# R409H.net
KiCad netlist of a schematic drawn in EAGLE
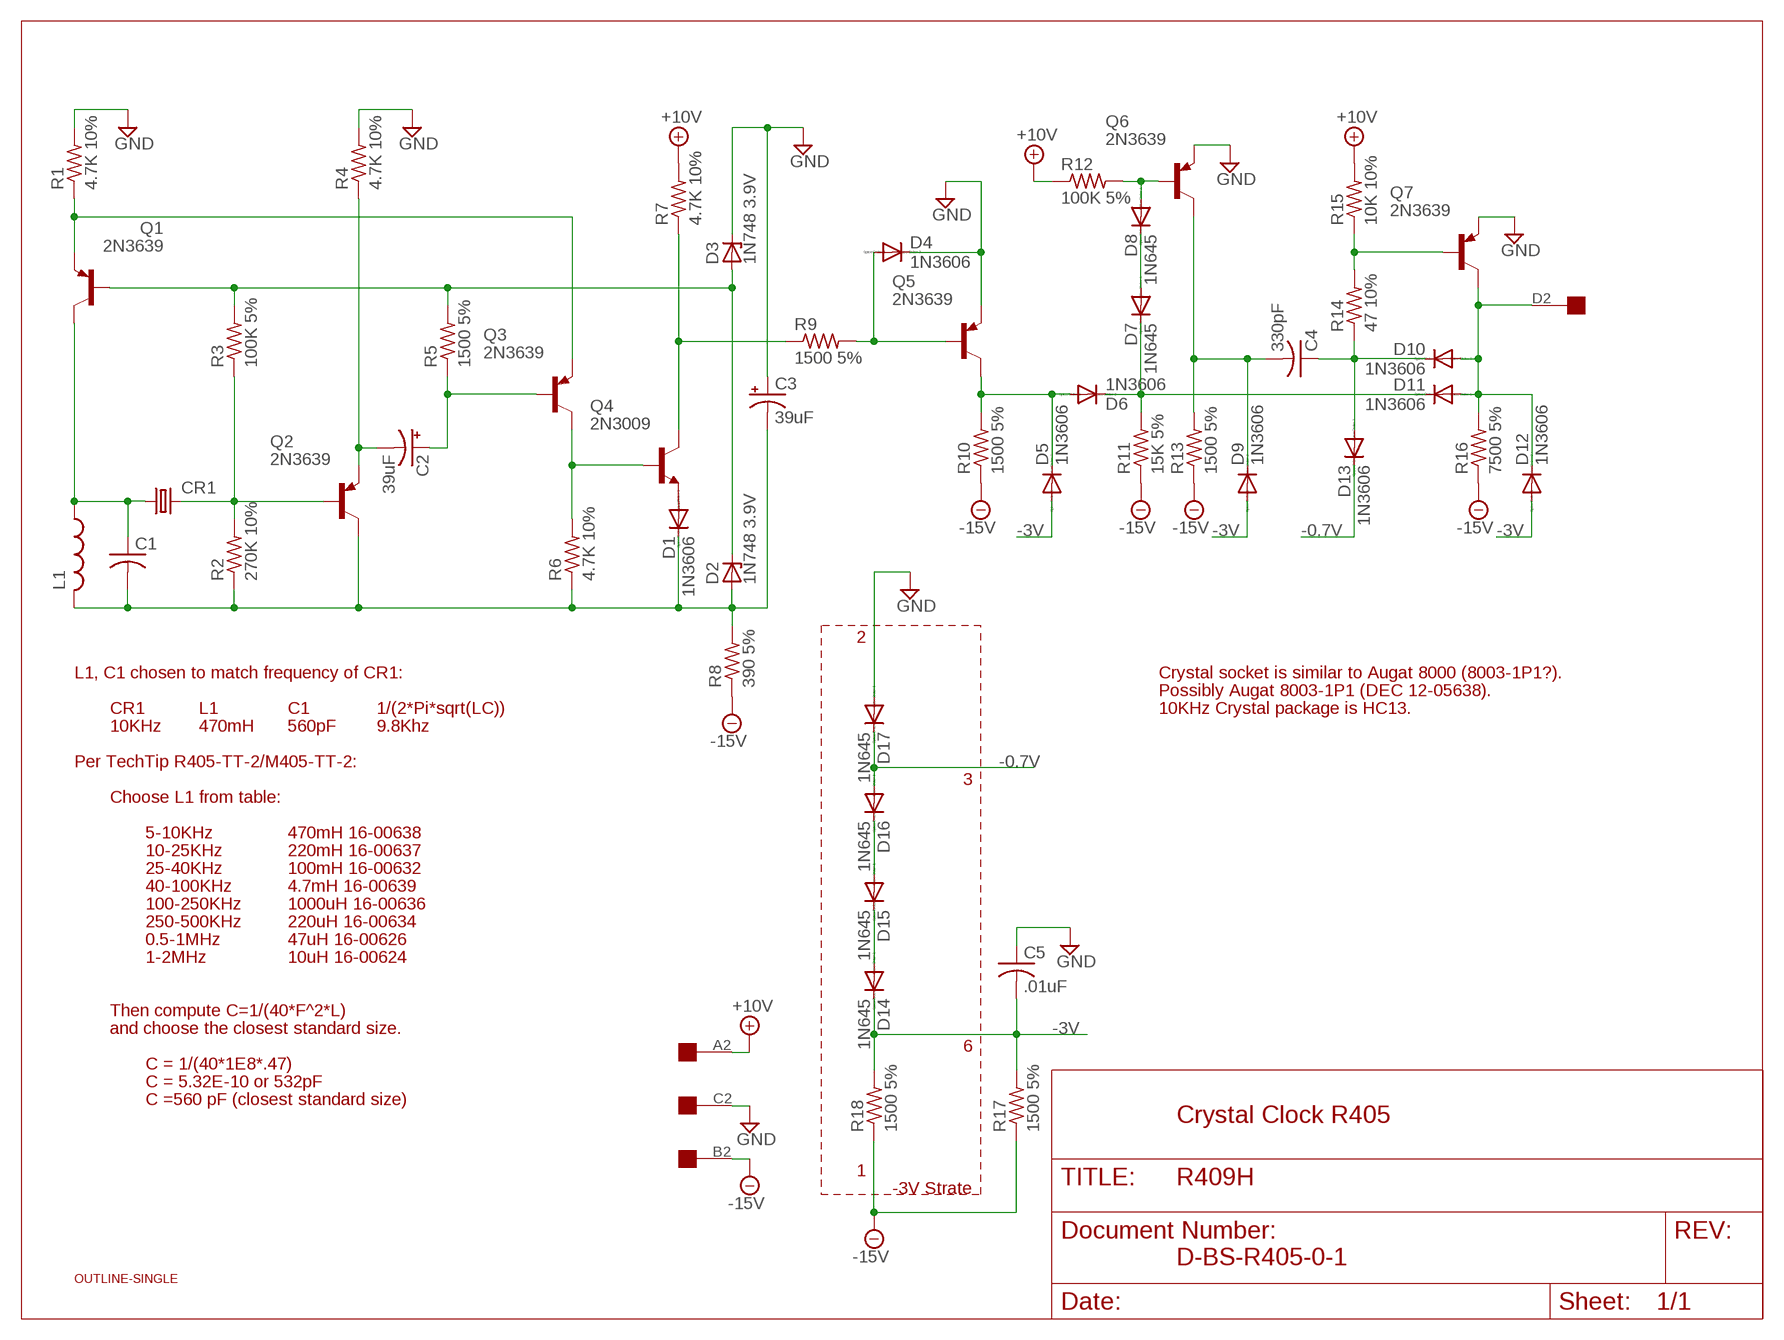
[diagram p0: schematic, sheet 1]

(export (version "E")
  (design (tool "Eeschema 10.0.6"))
  (components
    (comp (ref "C1")
      (value "C-US150-054X183")
      (footprint "eagle-import:C150-054X183")
      (libsource (lib "eagle-import") (part "C-US150-054X183"))
    )
    (comp (ref "C2")
      (value "39uF")
      (footprint "eagle-import:E15-5")
      (libsource (lib "eagle-import") (part "CPOL-USE15-5AXIAL"))
    )
    (comp (ref "C3")
      (value "39uF")
      (footprint "eagle-import:E15-5")
      (libsource (lib "eagle-import") (part "CPOL-USE15-5AXIAL"))
    )
    (comp (ref "C4")
      (value "330pF")
      (footprint "eagle-import:C150-054X183")
      (libsource (lib "eagle-import") (part "C-US150-054X183"))
    )
    (comp (ref "C5")
      (value ".01uF")
      (footprint "eagle-import:C150-054X183")
      (libsource (lib "eagle-import") (part "C-US150-054X183"))
    )
    (comp (ref "CR1")
      (value "CRYTALHC13U-H")
      (footprint "eagle-import:HC13U-H")
      (libsource (lib "eagle-import") (part "CRYTALHC13U-H"))
    )
    (comp (ref "D1")
      (value "1N3606")
      (footprint "eagle-import:DO35-10")
      (libsource (lib "eagle-import") (part "1N4148DO35-10"))
    )
    (comp (ref "D2")
      (value "1N748 3.9V")
      (footprint "eagle-import:DO35Z10")
      (libsource (lib "eagle-import") (part "ZENER-DIODEDO35Z10"))
    )
    (comp (ref "D3")
      (value "1N748 3.9V")
      (footprint "eagle-import:DO35Z10")
      (libsource (lib "eagle-import") (part "ZENER-DIODEDO35Z10"))
    )
    (comp (ref "D4")
      (value "1N3606")
      (footprint "eagle-import:DO35-10")
      (libsource (lib "eagle-import") (part "1N4148DO35-10"))
    )
    (comp (ref "D5")
      (value "1N3606")
      (footprint "eagle-import:DO35-10")
      (libsource (lib "eagle-import") (part "1N4148DO35-10"))
    )
    (comp (ref "D6")
      (value "1N3606")
      (footprint "eagle-import:DO35-10")
      (libsource (lib "eagle-import") (part "1N4148DO35-10"))
    )
    (comp (ref "D7")
      (value "1N645")
      (footprint "eagle-import:DO35-10")
      (libsource (lib "eagle-import") (part "1N4148DO35-10"))
    )
    (comp (ref "D8")
      (value "1N645")
      (footprint "eagle-import:DO35-10")
      (libsource (lib "eagle-import") (part "1N4148DO35-10"))
    )
    (comp (ref "D9")
      (value "1N3606")
      (footprint "eagle-import:DO35-10")
      (libsource (lib "eagle-import") (part "1N4148DO35-10"))
    )
    (comp (ref "D10")
      (value "1N3606")
      (footprint "eagle-import:DO35-10")
      (libsource (lib "eagle-import") (part "1N4148DO35-10"))
    )
    (comp (ref "D11")
      (value "1N3606")
      (footprint "eagle-import:DO35-10")
      (libsource (lib "eagle-import") (part "1N4148DO35-10"))
    )
    (comp (ref "D12")
      (value "1N3606")
      (footprint "eagle-import:DO35-10")
      (libsource (lib "eagle-import") (part "1N4148DO35-10"))
    )
    (comp (ref "D13")
      (value "1N3606")
      (footprint "eagle-import:DO35-10")
      (libsource (lib "eagle-import") (part "1N4148DO35-10"))
    )
    (comp (ref "D14")
      (value "1N645")
      (footprint "eagle-import:DO35-10")
      (libsource (lib "eagle-import") (part "1N4148DO35-10"))
    )
    (comp (ref "D15")
      (value "1N645")
      (footprint "eagle-import:DO35-10")
      (libsource (lib "eagle-import") (part "1N4148DO35-10"))
    )
    (comp (ref "D16")
      (value "1N645")
      (footprint "eagle-import:DO35-10")
      (libsource (lib "eagle-import") (part "1N4148DO35-10"))
    )
    (comp (ref "D17")
      (value "1N645")
      (footprint "eagle-import:DO35-10")
      (libsource (lib "eagle-import") (part "1N4148DO35-10"))
    )
    (comp (ref "L1")
      (value "L-US0207/7")
      (footprint "eagle-import:0207_7")
      (libsource (lib "eagle-import") (part "L-US0207/7"))
    )
    (comp (ref "Q1")
      (value "2N3639")
      (footprint "eagle-import:TO39")
      (libsource (lib "eagle-import") (part "2N2904"))
    )
    (comp (ref "Q2")
      (value "2N3639")
      (footprint "eagle-import:TO39")
      (libsource (lib "eagle-import") (part "2N2904"))
    )
    (comp (ref "Q3")
      (value "2N3639")
      (footprint "eagle-import:TO39")
      (libsource (lib "eagle-import") (part "2N2904"))
    )
    (comp (ref "Q4")
      (value "2N3009")
      (footprint "eagle-import:TO5")
      (libsource (lib "eagle-import") (part "2N2102"))
    )
    (comp (ref "Q5")
      (value "2N3639")
      (footprint "eagle-import:TO39")
      (libsource (lib "eagle-import") (part "2N2904"))
    )
    (comp (ref "Q6")
      (value "2N3639")
      (footprint "eagle-import:TO39")
      (libsource (lib "eagle-import") (part "2N2904"))
    )
    (comp (ref "Q7")
      (value "2N3639")
      (footprint "eagle-import:TO39")
      (libsource (lib "eagle-import") (part "2N2904"))
    )
    (comp (ref "R1")
      (value "4.7K 10%")
      (footprint "eagle-import:0207_10")
      (libsource (lib "eagle-import") (part "R-US_0207/10"))
    )
    (comp (ref "R2")
      (value "270K 10%")
      (footprint "eagle-import:0207_10")
      (libsource (lib "eagle-import") (part "R-US_0207/10"))
    )
    (comp (ref "R3")
      (value "100K 5%")
      (footprint "eagle-import:0207_10")
      (libsource (lib "eagle-import") (part "R-US_0207/10"))
    )
    (comp (ref "R4")
      (value "4.7K 10%")
      (footprint "eagle-import:0207_10")
      (libsource (lib "eagle-import") (part "R-US_0207/10"))
    )
    (comp (ref "R5")
      (value "1500 5%")
      (footprint "eagle-import:0207_10")
      (libsource (lib "eagle-import") (part "R-US_0207/10"))
    )
    (comp (ref "R6")
      (value "4.7K 10%")
      (footprint "eagle-import:0207_10")
      (libsource (lib "eagle-import") (part "R-US_0207/10"))
    )
    (comp (ref "R7")
      (value "4.7K 10%")
      (footprint "eagle-import:0207_10")
      (libsource (lib "eagle-import") (part "R-US_0207/10"))
    )
    (comp (ref "R8")
      (value "390 5%")
      (footprint "eagle-import:0207_10")
      (libsource (lib "eagle-import") (part "R-US_0207/10"))
    )
    (comp (ref "R9")
      (value "1500 5%")
      (footprint "eagle-import:0207_10")
      (libsource (lib "eagle-import") (part "R-US_0207/10"))
    )
    (comp (ref "R10")
      (value "1500 5%")
      (footprint "eagle-import:0207_10")
      (libsource (lib "eagle-import") (part "R-US_0207/10"))
    )
    (comp (ref "R11")
      (value "15K 5%")
      (footprint "eagle-import:0207_10")
      (libsource (lib "eagle-import") (part "R-US_0207/10"))
    )
    (comp (ref "R12")
      (value "100K 5%")
      (footprint "eagle-import:0207_10")
      (libsource (lib "eagle-import") (part "R-US_0207/10"))
    )
    (comp (ref "R13")
      (value "1500 5%")
      (footprint "eagle-import:0207_10")
      (libsource (lib "eagle-import") (part "R-US_0207/10"))
    )
    (comp (ref "R14")
      (value "47 10%")
      (footprint "eagle-import:0207_10")
      (libsource (lib "eagle-import") (part "R-US_0207/10"))
    )
    (comp (ref "R15")
      (value "10K 10%")
      (footprint "eagle-import:0207_10")
      (libsource (lib "eagle-import") (part "R-US_0207/10"))
    )
    (comp (ref "R16")
      (value "7500 5%")
      (footprint "eagle-import:0207_10")
      (libsource (lib "eagle-import") (part "R-US_0207/10"))
    )
    (comp (ref "R17")
      (value "1500 5%")
      (footprint "eagle-import:0207_10")
      (libsource (lib "eagle-import") (part "R-US_0207/10"))
    )
    (comp (ref "R18")
      (value "1500 5%")
      (footprint "eagle-import:0207_10")
      (libsource (lib "eagle-import") (part "R-US_0207/10"))
    )
    (comp (ref "U$1")
      (value "OUTLINE-SINGLE")
      (footprint "eagle-import:SINGLE")
      (libsource (lib "eagle-import") (part "OUTLINE-SINGLE"))
    )
    (comp (ref "U$2")
      (value "EDGE-1")
      (footprint "eagle-import:EDGE-CON1")
      (libsource (lib "eagle-import") (part "EDGE-1"))
    )
  )
  (nets
    (net (code "1") (name "+10V") (class "Default")
      (node (ref "R12") (pin "1") (pinfunction "1_1") (pintype "passive"))
      (node (ref "R15") (pin "2") (pinfunction "2_2") (pintype "passive"))
      (node (ref "R7") (pin "2") (pinfunction "2_2") (pintype "passive"))
      (node (ref "U$2") (pin "A2") (pinfunction "1_A2") (pintype "bidirectional"))
    )
    (net (code "2") (name "-15V") (class "Default")
      (node (ref "R10") (pin "1") (pinfunction "1_1") (pintype "passive"))
      (node (ref "R11") (pin "1") (pinfunction "1_1") (pintype "passive"))
      (node (ref "R13") (pin "1") (pinfunction "1_1") (pintype "passive"))
      (node (ref "R16") (pin "1") (pinfunction "1_1") (pintype "passive"))
      (node (ref "R17") (pin "1") (pinfunction "1_1") (pintype "passive"))
      (node (ref "R18") (pin "1") (pinfunction "1_1") (pintype "passive"))
      (node (ref "R8") (pin "1") (pinfunction "1_1") (pintype "passive"))
      (node (ref "U$2") (pin "B2") (pinfunction "1_B2") (pintype "bidirectional"))
    )
    (net (code "3") (name "/-0.7V") (class "Default")
      (node (ref "D13") (pin "C") (pinfunction "C_C") (pintype "passive"))
      (node (ref "D16") (pin "A") (pinfunction "A_A") (pintype "passive"))
      (node (ref "D17") (pin "C") (pinfunction "C_C") (pintype "passive"))
    )
    (net (code "4") (name "/-3V") (class "Default")
      (node (ref "C5") (pin "2") (pinfunction "2_2") (pintype "passive"))
      (node (ref "D12") (pin "A") (pinfunction "A_A") (pintype "passive"))
      (node (ref "D14") (pin "C") (pinfunction "C_C") (pintype "passive"))
      (node (ref "D5") (pin "A") (pinfunction "A_A") (pintype "passive"))
      (node (ref "D9") (pin "A") (pinfunction "A_A") (pintype "passive"))
      (node (ref "R17") (pin "2") (pinfunction "2_2") (pintype "passive"))
      (node (ref "R18") (pin "2") (pinfunction "2_2") (pintype "passive"))
    )
    (net (code "5") (name "GND") (class "Default")
      (node (ref "C3") (pin "+") (pinfunction "+_+") (pintype "passive"))
      (node (ref "C5") (pin "1") (pinfunction "1_1") (pintype "passive"))
      (node (ref "D17") (pin "A") (pinfunction "A_A") (pintype "passive"))
      (node (ref "D3") (pin "C") (pinfunction "C_C") (pintype "passive"))
      (node (ref "D4") (pin "C") (pinfunction "C_C") (pintype "passive"))
      (node (ref "Q5") (pin "1") (pinfunction "E_1") (pintype "passive"))
      (node (ref "Q6") (pin "1") (pinfunction "E_1") (pintype "passive"))
      (node (ref "Q7") (pin "1") (pinfunction "E_1") (pintype "passive"))
      (node (ref "R1") (pin "2") (pinfunction "2_2") (pintype "passive"))
      (node (ref "R4") (pin "2") (pinfunction "2_2") (pintype "passive"))
      (node (ref "U$2") (pin "C2") (pinfunction "1_C2") (pintype "bidirectional"))
    )
    (net (code "6") (name "Net-(C4-Pad1)") (class "Default")
      (node (ref "C4") (pin "1") (pinfunction "1_1") (pintype "passive"))
      (node (ref "D10") (pin "C") (pinfunction "C_C") (pintype "passive"))
      (node (ref "D13") (pin "A") (pinfunction "A_A") (pintype "passive"))
      (node (ref "R14") (pin "1") (pinfunction "1_1") (pintype "passive"))
    )
    (net (code "7") (name "Net-(D7-PadA)") (class "Default")
      (node (ref "D7") (pin "A") (pinfunction "A_A") (pintype "passive"))
      (node (ref "D8") (pin "C") (pinfunction "C_C") (pintype "passive"))
    )
    (net (code "8") (name "Net-(D11-PadC)") (class "Default")
      (node (ref "D11") (pin "C") (pinfunction "C_C") (pintype "passive"))
      (node (ref "D6") (pin "C") (pinfunction "C_C") (pintype "passive"))
      (node (ref "D7") (pin "C") (pinfunction "C_C") (pintype "passive"))
      (node (ref "R11") (pin "2") (pinfunction "2_2") (pintype "passive"))
    )
    (net (code "9") (name "Net-(D14-PadA)") (class "Default")
      (node (ref "D14") (pin "A") (pinfunction "A_A") (pintype "passive"))
      (node (ref "D15") (pin "C") (pinfunction "C_C") (pintype "passive"))
    )
    (net (code "10") (name "Net-(D15-PadA)") (class "Default")
      (node (ref "D15") (pin "A") (pinfunction "A_A") (pintype "passive"))
      (node (ref "D16") (pin "C") (pinfunction "C_C") (pintype "passive"))
    )
    (net (code "11") (name "Net-(Q1-B)") (class "Default")
      (node (ref "D2") (pin "C") (pinfunction "C_C") (pintype "passive"))
      (node (ref "D3") (pin "A") (pinfunction "A_A") (pintype "passive"))
      (node (ref "Q1") (pin "2") (pinfunction "B_2") (pintype "passive"))
      (node (ref "R3") (pin "2") (pinfunction "2_2") (pintype "passive"))
      (node (ref "R5") (pin "2") (pinfunction "2_2") (pintype "passive"))
    )
    (net (code "12") (name "Net-(Q1-C)") (class "Default")
      (node (ref "C1") (pin "1") (pinfunction "1_1") (pintype "passive"))
      (node (ref "CR1") (pin "1") (pinfunction "1_1") (pintype "passive"))
      (node (ref "L1") (pin "1") (pinfunction "1_1") (pintype "passive"))
      (node (ref "Q1") (pin "3") (pinfunction "C_3") (pintype "passive"))
    )
    (net (code "13") (name "Net-(Q1-E)") (class "Default")
      (node (ref "Q1") (pin "1") (pinfunction "E_1") (pintype "passive"))
      (node (ref "Q3") (pin "1") (pinfunction "E_1") (pintype "passive"))
      (node (ref "R1") (pin "1") (pinfunction "1_1") (pintype "passive"))
    )
    (net (code "14") (name "Net-(Q2-B)") (class "Default")
      (node (ref "CR1") (pin "2") (pinfunction "2_2") (pintype "passive"))
      (node (ref "Q2") (pin "2") (pinfunction "B_2") (pintype "passive"))
      (node (ref "R2") (pin "2") (pinfunction "2_2") (pintype "passive"))
      (node (ref "R3") (pin "1") (pinfunction "1_1") (pintype "passive"))
    )
    (net (code "15") (name "Net-(Q2-C)") (class "Default")
      (node (ref "C1") (pin "2") (pinfunction "2_2") (pintype "passive"))
      (node (ref "C3") (pin "-") (pinfunction "-_-") (pintype "passive"))
      (node (ref "D1") (pin "C") (pinfunction "C_C") (pintype "passive"))
      (node (ref "D2") (pin "A") (pinfunction "A_A") (pintype "passive"))
      (node (ref "L1") (pin "2") (pinfunction "2_2") (pintype "passive"))
      (node (ref "Q2") (pin "3") (pinfunction "C_3") (pintype "passive"))
      (node (ref "R2") (pin "1") (pinfunction "1_1") (pintype "passive"))
      (node (ref "R6") (pin "1") (pinfunction "1_1") (pintype "passive"))
      (node (ref "R8") (pin "2") (pinfunction "2_2") (pintype "passive"))
    )
    (net (code "16") (name "Net-(Q2-E)") (class "Default")
      (node (ref "C2") (pin "-") (pinfunction "-_-") (pintype "passive"))
      (node (ref "Q2") (pin "1") (pinfunction "E_1") (pintype "passive"))
      (node (ref "R4") (pin "1") (pinfunction "1_1") (pintype "passive"))
    )
    (net (code "17") (name "Net-(Q3-B)") (class "Default")
      (node (ref "C2") (pin "+") (pinfunction "+_+") (pintype "passive"))
      (node (ref "Q3") (pin "2") (pinfunction "B_2") (pintype "passive"))
      (node (ref "R5") (pin "1") (pinfunction "1_1") (pintype "passive"))
    )
    (net (code "18") (name "Net-(Q3-C)") (class "Default")
      (node (ref "Q3") (pin "3") (pinfunction "C_3") (pintype "passive"))
      (node (ref "Q4") (pin "2") (pinfunction "B_2") (pintype "passive"))
      (node (ref "R6") (pin "2") (pinfunction "2_2") (pintype "passive"))
    )
    (net (code "19") (name "Net-(Q4-C)") (class "Default")
      (node (ref "Q4") (pin "3") (pinfunction "C_3") (pintype "passive"))
      (node (ref "R7") (pin "1") (pinfunction "1_1") (pintype "passive"))
      (node (ref "R9") (pin "1") (pinfunction "1_1") (pintype "passive"))
    )
    (net (code "20") (name "Net-(Q4-E)") (class "Default")
      (node (ref "D1") (pin "A") (pinfunction "A_A") (pintype "passive"))
      (node (ref "Q4") (pin "1") (pinfunction "E_1") (pintype "passive"))
    )
    (net (code "21") (name "Net-(Q5-B)") (class "Default")
      (node (ref "D4") (pin "A") (pinfunction "A_A") (pintype "passive"))
      (node (ref "Q5") (pin "2") (pinfunction "B_2") (pintype "passive"))
      (node (ref "R9") (pin "2") (pinfunction "2_2") (pintype "passive"))
    )
    (net (code "22") (name "Net-(Q5-C)") (class "Default")
      (node (ref "D5") (pin "C") (pinfunction "C_C") (pintype "passive"))
      (node (ref "D6") (pin "A") (pinfunction "A_A") (pintype "passive"))
      (node (ref "Q5") (pin "3") (pinfunction "C_3") (pintype "passive"))
      (node (ref "R10") (pin "2") (pinfunction "2_2") (pintype "passive"))
    )
    (net (code "23") (name "Net-(Q6-B)") (class "Default")
      (node (ref "D8") (pin "A") (pinfunction "A_A") (pintype "passive"))
      (node (ref "Q6") (pin "2") (pinfunction "B_2") (pintype "passive"))
      (node (ref "R12") (pin "2") (pinfunction "2_2") (pintype "passive"))
    )
    (net (code "24") (name "Net-(Q6-C)") (class "Default")
      (node (ref "C4") (pin "2") (pinfunction "2_2") (pintype "passive"))
      (node (ref "D9") (pin "C") (pinfunction "C_C") (pintype "passive"))
      (node (ref "Q6") (pin "3") (pinfunction "C_3") (pintype "passive"))
      (node (ref "R13") (pin "2") (pinfunction "2_2") (pintype "passive"))
    )
    (net (code "25") (name "Net-(Q7-B)") (class "Default")
      (node (ref "Q7") (pin "2") (pinfunction "B_2") (pintype "passive"))
      (node (ref "R14") (pin "2") (pinfunction "2_2") (pintype "passive"))
      (node (ref "R15") (pin "1") (pinfunction "1_1") (pintype "passive"))
    )
    (net (code "26") (name "Net-(Q7-C)") (class "Default")
      (node (ref "D10") (pin "A") (pinfunction "A_A") (pintype "passive"))
      (node (ref "D11") (pin "A") (pinfunction "A_A") (pintype "passive"))
      (node (ref "D12") (pin "C") (pinfunction "C_C") (pintype "passive"))
      (node (ref "Q7") (pin "3") (pinfunction "C_3") (pintype "passive"))
      (node (ref "R16") (pin "2") (pinfunction "2_2") (pintype "passive"))
      (node (ref "U$2") (pin "D2") (pinfunction "1_D2") (pintype "bidirectional"))
    )
  )
)
